# Molex_Breakout_Board.net
KiCad netlist of a schematic drawn in EAGLE
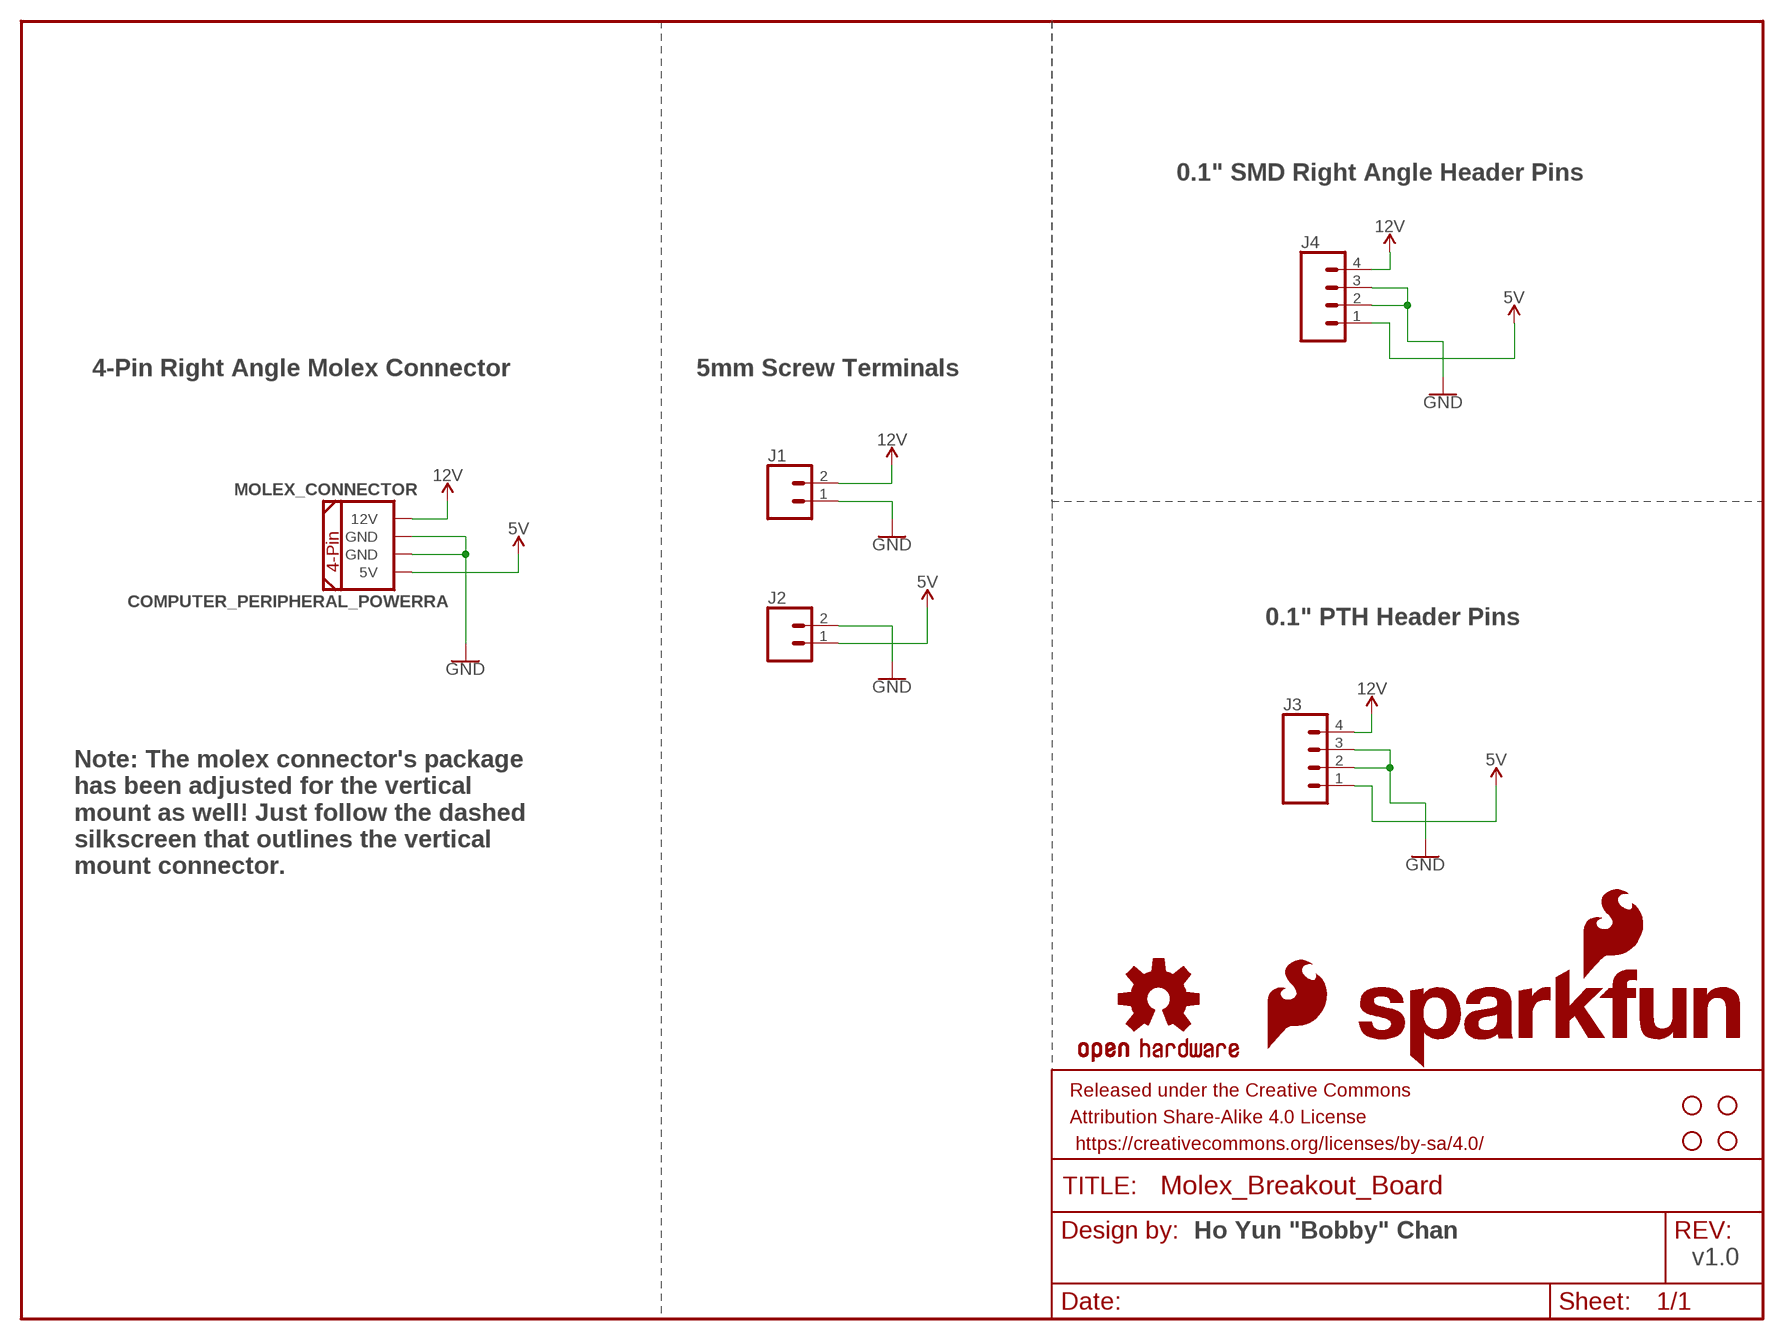
[diagram p0: schematic, sheet 1]

(export (version "E")
  (design (tool "Eeschema 10.0.6"))
  (components
    (comp (ref "FRAME1")
      (value "FRAME-LETTER")
      (footprint "eagle-import:CREATIVE_COMMONS")
      (libsource (lib "eagle-import") (part "FRAME-LETTER"))
    )
    (comp (ref "H1")
      (value "STAND-OFF")
      (footprint "eagle-import:STAND-OFF")
      (libsource (lib "eagle-import") (part "STAND-OFF"))
    )
    (comp (ref "H2")
      (value "STAND-OFF")
      (footprint "eagle-import:STAND-OFF")
      (libsource (lib "eagle-import") (part "STAND-OFF"))
    )
    (comp (ref "H3")
      (value "STAND-OFF")
      (footprint "eagle-import:STAND-OFF")
      (libsource (lib "eagle-import") (part "STAND-OFF"))
    )
    (comp (ref "H4")
      (value "STAND-OFF")
      (footprint "eagle-import:STAND-OFF")
      (libsource (lib "eagle-import") (part "STAND-OFF"))
    )
    (comp (ref "J1")
      (value "CONN_025MM")
      (footprint "eagle-import:SCREWTERMINAL-5MM-2")
      (libsource (lib "eagle-import") (part "CONN_025MM"))
    )
    (comp (ref "J2")
      (value "CONN_025MM")
      (footprint "eagle-import:SCREWTERMINAL-5MM-2")
      (libsource (lib "eagle-import") (part "CONN_025MM"))
    )
    (comp (ref "J3")
      (value "CONN_04")
      (footprint "eagle-import:1X04")
      (libsource (lib "eagle-import") (part "CONN_04"))
    )
    (comp (ref "J4")
      (value "CONN_04SMD")
      (footprint "eagle-import:1X04_SMD_RA_MALE")
      (libsource (lib "eagle-import") (part "CONN_04SMD"))
    )
    (comp (ref "LOGO1")
      (value "OSHW-LOGOS")
      (footprint "eagle-import:OSHW-LOGO-S")
      (libsource (lib "eagle-import") (part "OSHW-LOGOS"))
    )
    (comp (ref "LOGO2")
      (value "SFE_LOGO_NAME_FLAME.1_INCH")
      (footprint "eagle-import:SFE_LOGO_NAME_FLAME_.1")
      (libsource (lib "eagle-import") (part "SFE_LOGO_NAME_FLAME.1_INCH"))
    )
    (comp (ref "LOGO3")
      (value "SFE_LOGO_FLAME.1_INCH")
      (footprint "eagle-import:SFE_LOGO_FLAME_.1")
      (libsource (lib "eagle-import") (part "SFE_LOGO_FLAME.1_INCH"))
    )
    (comp (ref "MOLEX_CONNECTOR")
      (value "COMPUTER_PERIPHERAL_POWERRA")
      (footprint "eagle-import:COMPUTER-PERIPHERAL-POWER-RA")
      (libsource (lib "eagle-import") (part "COMPUTER_PERIPHERAL_POWERRA"))
    )
  )
  (nets
    (net (code "1") (name "5V") (class "Default")
      (node (ref "J2") (pin "1") (pinfunction "1_1") (pintype "passive"))
      (node (ref "J3") (pin "1") (pinfunction "1_1") (pintype "passive"))
      (node (ref "J4") (pin "1") (pinfunction "1_1") (pintype "passive"))
      (node (ref "MOLEX_CONNECTOR") (pin "5V") (pinfunction "5V_5V") (pintype "passive"))
    )
    (net (code "2") (name "12V") (class "Default")
      (node (ref "J1") (pin "2") (pinfunction "2_2") (pintype "passive"))
      (node (ref "J3") (pin "4") (pinfunction "4_4") (pintype "passive"))
      (node (ref "J4") (pin "4") (pinfunction "4_4") (pintype "passive"))
      (node (ref "MOLEX_CONNECTOR") (pin "12V") (pinfunction "12V_12V") (pintype "passive"))
    )
    (net (code "3") (name "GND") (class "Default")
      (node (ref "J1") (pin "1") (pinfunction "1_1") (pintype "passive"))
      (node (ref "J2") (pin "2") (pinfunction "2_2") (pintype "passive"))
      (node (ref "J3") (pin "2") (pinfunction "2_2") (pintype "passive"))
      (node (ref "J3") (pin "3") (pinfunction "3_3") (pintype "passive"))
      (node (ref "J4") (pin "2") (pinfunction "2_2") (pintype "passive"))
      (node (ref "J4") (pin "3") (pinfunction "3_3") (pintype "passive"))
      (node (ref "MOLEX_CONNECTOR") (pin "GND@1") (pinfunction "GND_GND@1") (pintype "passive"))
      (node (ref "MOLEX_CONNECTOR") (pin "GND@2") (pinfunction "GND_GND@2") (pintype "passive"))
    )
  )
)
